# solenoidDriver.net
KiCad netlist of a schematic drawn in EAGLE
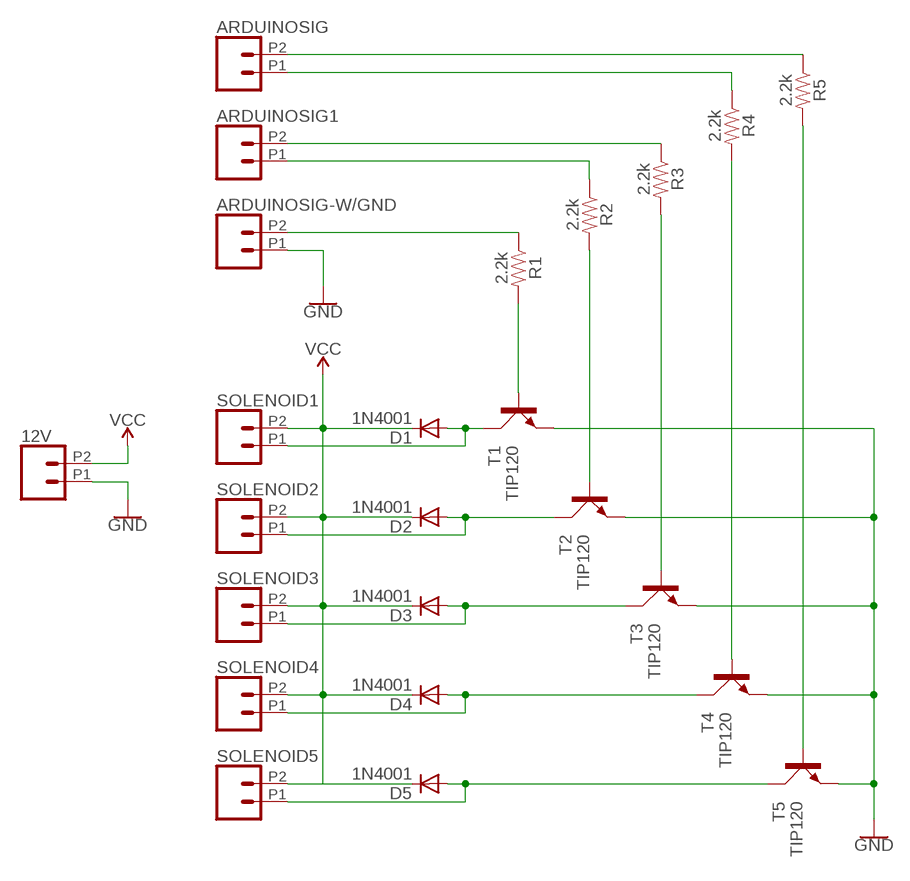
[diagram p0: schematic, sheet 1]

(export (version "E")
  (design (tool "Eeschema 10.0.6"))
  (components
    (comp (ref "12V")
      (value "CONN_022.54MM_SCREWTERM")
      (footprint "eagle-import:1X02_2.54_SCREWTERM")
      (libsource (lib "eagle-import") (part "CONN_022.54MM_SCREWTERM"))
    )
    (comp (ref "ARDUINOSIG")
      (value "CONN_022.54MM_SCREWTERM")
      (footprint "eagle-import:1X02_2.54_SCREWTERM")
      (libsource (lib "eagle-import") (part "CONN_022.54MM_SCREWTERM"))
    )
    (comp (ref "ARDUINOSIG-W/GND")
      (value "CONN_022.54MM_SCREWTERM")
      (footprint "eagle-import:1X02_2.54_SCREWTERM")
      (libsource (lib "eagle-import") (part "CONN_022.54MM_SCREWTERM"))
    )
    (comp (ref "ARDUINOSIG1")
      (value "CONN_022.54MM_SCREWTERM")
      (footprint "eagle-import:1X02_2.54_SCREWTERM")
      (libsource (lib "eagle-import") (part "CONN_022.54MM_SCREWTERM"))
    )
    (comp (ref "D1")
      (value "1N4001")
      (footprint "eagle-import:DO41-10")
      (libsource (lib "eagle-import") (part "1N4004"))
    )
    (comp (ref "D2")
      (value "1N4001")
      (footprint "eagle-import:DO41-10")
      (libsource (lib "eagle-import") (part "1N4004"))
    )
    (comp (ref "D3")
      (value "1N4001")
      (footprint "eagle-import:DO41-10")
      (libsource (lib "eagle-import") (part "1N4004"))
    )
    (comp (ref "D4")
      (value "1N4001")
      (footprint "eagle-import:DO41-10")
      (libsource (lib "eagle-import") (part "1N4004"))
    )
    (comp (ref "D5")
      (value "1N4001")
      (footprint "eagle-import:DO41-10")
      (libsource (lib "eagle-import") (part "1N4004"))
    )
    (comp (ref "R1")
      (value "2.2k")
      (footprint "eagle-import:AXIAL-0.3-KIT")
      (libsource (lib "eagle-import") (part "10KOHM-HORIZ_KIT-1/4W-1%"))
    )
    (comp (ref "R2")
      (value "2.2k")
      (footprint "eagle-import:AXIAL-0.3-KIT")
      (libsource (lib "eagle-import") (part "10KOHM-HORIZ_KIT-1/4W-1%"))
    )
    (comp (ref "R3")
      (value "2.2k")
      (footprint "eagle-import:AXIAL-0.3-KIT")
      (libsource (lib "eagle-import") (part "10KOHM-HORIZ_KIT-1/4W-1%"))
    )
    (comp (ref "R4")
      (value "2.2k")
      (footprint "eagle-import:AXIAL-0.3-KIT")
      (libsource (lib "eagle-import") (part "10KOHM-HORIZ_KIT-1/4W-1%"))
    )
    (comp (ref "R5")
      (value "2.2k")
      (footprint "eagle-import:AXIAL-0.3-KIT")
      (libsource (lib "eagle-import") (part "10KOHM-HORIZ_KIT-1/4W-1%"))
    )
    (comp (ref "SOLENOID1")
      (value "CONN_022.54MM_SCREWTERM")
      (footprint "eagle-import:1X02_2.54_SCREWTERM")
      (libsource (lib "eagle-import") (part "CONN_022.54MM_SCREWTERM"))
    )
    (comp (ref "SOLENOID2")
      (value "CONN_022.54MM_SCREWTERM")
      (footprint "eagle-import:1X02_2.54_SCREWTERM")
      (libsource (lib "eagle-import") (part "CONN_022.54MM_SCREWTERM"))
    )
    (comp (ref "SOLENOID3")
      (value "CONN_022.54MM_SCREWTERM")
      (footprint "eagle-import:1X02_2.54_SCREWTERM")
      (libsource (lib "eagle-import") (part "CONN_022.54MM_SCREWTERM"))
    )
    (comp (ref "SOLENOID4")
      (value "CONN_022.54MM_SCREWTERM")
      (footprint "eagle-import:1X02_2.54_SCREWTERM")
      (libsource (lib "eagle-import") (part "CONN_022.54MM_SCREWTERM"))
    )
    (comp (ref "SOLENOID5")
      (value "CONN_022.54MM_SCREWTERM")
      (footprint "eagle-import:1X02_2.54_SCREWTERM")
      (libsource (lib "eagle-import") (part "CONN_022.54MM_SCREWTERM"))
    )
    (comp (ref "T1")
      (value "TIP120")
      (footprint "eagle-import:TO220AH-NOHOLE")
      (libsource (lib "eagle-import") (part "TIP120-NOHOLE"))
    )
    (comp (ref "T2")
      (value "TIP120")
      (footprint "eagle-import:TO220AH-NOHOLE")
      (libsource (lib "eagle-import") (part "TIP120-NOHOLE"))
    )
    (comp (ref "T3")
      (value "TIP120")
      (footprint "eagle-import:TO220AH-NOHOLE")
      (libsource (lib "eagle-import") (part "TIP120-NOHOLE"))
    )
    (comp (ref "T4")
      (value "TIP120")
      (footprint "eagle-import:TO220AH-NOHOLE")
      (libsource (lib "eagle-import") (part "TIP120-NOHOLE"))
    )
    (comp (ref "T5")
      (value "TIP120")
      (footprint "eagle-import:TO220AH-NOHOLE")
      (libsource (lib "eagle-import") (part "TIP120-NOHOLE"))
    )
  )
  (nets
    (net (code "1") (name "GND") (class "Default")
      (node (ref "12V") (pin "P1") (pinfunction "1_P1") (pintype "passive"))
      (node (ref "ARDUINOSIG-W/GND") (pin "P1") (pinfunction "1_P1") (pintype "passive"))
      (node (ref "T1") (pin "E") (pinfunction "E_E") (pintype "passive"))
      (node (ref "T2") (pin "E") (pinfunction "E_E") (pintype "passive"))
      (node (ref "T3") (pin "E") (pinfunction "E_E") (pintype "passive"))
      (node (ref "T4") (pin "E") (pinfunction "E_E") (pintype "passive"))
      (node (ref "T5") (pin "E") (pinfunction "E_E") (pintype "passive"))
    )
    (net (code "2") (name "Net-(ARDUINOSIG-1)") (class "Default")
      (node (ref "ARDUINOSIG") (pin "P1") (pinfunction "1_P1") (pintype "passive"))
      (node (ref "R4") (pin "P$1") (pinfunction "1_P$1") (pintype "passive"))
    )
    (net (code "3") (name "Net-(ARDUINOSIG-2)") (class "Default")
      (node (ref "ARDUINOSIG") (pin "P2") (pinfunction "2_P2") (pintype "passive"))
      (node (ref "R5") (pin "P$1") (pinfunction "1_P$1") (pintype "passive"))
    )
    (net (code "4") (name "Net-(ARDUINOSIG-W/GND-2)") (class "Default")
      (node (ref "ARDUINOSIG-W/GND") (pin "P2") (pinfunction "2_P2") (pintype "passive"))
      (node (ref "R1") (pin "P$1") (pinfunction "1_P$1") (pintype "passive"))
    )
    (net (code "5") (name "Net-(ARDUINOSIG1-1)") (class "Default")
      (node (ref "ARDUINOSIG1") (pin "P1") (pinfunction "1_P1") (pintype "passive"))
      (node (ref "R2") (pin "P$1") (pinfunction "1_P$1") (pintype "passive"))
    )
    (net (code "6") (name "Net-(ARDUINOSIG1-2)") (class "Default")
      (node (ref "ARDUINOSIG1") (pin "P2") (pinfunction "2_P2") (pintype "passive"))
      (node (ref "R3") (pin "P$1") (pinfunction "1_P$1") (pintype "passive"))
    )
    (net (code "7") (name "Net-(R1-2)") (class "Default")
      (node (ref "R1") (pin "P$2") (pinfunction "2_P$2") (pintype "passive"))
      (node (ref "T1") (pin "B") (pinfunction "B_B") (pintype "passive"))
    )
    (net (code "8") (name "Net-(R2-2)") (class "Default")
      (node (ref "R2") (pin "P$2") (pinfunction "2_P$2") (pintype "passive"))
      (node (ref "T2") (pin "B") (pinfunction "B_B") (pintype "passive"))
    )
    (net (code "9") (name "Net-(R3-2)") (class "Default")
      (node (ref "R3") (pin "P$2") (pinfunction "2_P$2") (pintype "passive"))
      (node (ref "T3") (pin "B") (pinfunction "B_B") (pintype "passive"))
    )
    (net (code "10") (name "Net-(R4-2)") (class "Default")
      (node (ref "R4") (pin "P$2") (pinfunction "2_P$2") (pintype "passive"))
      (node (ref "T4") (pin "B") (pinfunction "B_B") (pintype "passive"))
    )
    (net (code "11") (name "Net-(R5-2)") (class "Default")
      (node (ref "R5") (pin "P$2") (pinfunction "2_P$2") (pintype "passive"))
      (node (ref "T5") (pin "B") (pinfunction "B_B") (pintype "passive"))
    )
    (net (code "12") (name "Net-(SOLENOID1-1)") (class "Default")
      (node (ref "D1") (pin "A") (pinfunction "A_A") (pintype "passive"))
      (node (ref "SOLENOID1") (pin "P1") (pinfunction "1_P1") (pintype "passive"))
      (node (ref "T1") (pin "C") (pinfunction "C_C") (pintype "passive"))
    )
    (net (code "13") (name "Net-(SOLENOID2-1)") (class "Default")
      (node (ref "D2") (pin "A") (pinfunction "A_A") (pintype "passive"))
      (node (ref "SOLENOID2") (pin "P1") (pinfunction "1_P1") (pintype "passive"))
      (node (ref "T2") (pin "C") (pinfunction "C_C") (pintype "passive"))
    )
    (net (code "14") (name "Net-(SOLENOID3-1)") (class "Default")
      (node (ref "D3") (pin "A") (pinfunction "A_A") (pintype "passive"))
      (node (ref "SOLENOID3") (pin "P1") (pinfunction "1_P1") (pintype "passive"))
      (node (ref "T3") (pin "C") (pinfunction "C_C") (pintype "passive"))
    )
    (net (code "15") (name "Net-(SOLENOID4-1)") (class "Default")
      (node (ref "D4") (pin "A") (pinfunction "A_A") (pintype "passive"))
      (node (ref "SOLENOID4") (pin "P1") (pinfunction "1_P1") (pintype "passive"))
      (node (ref "T4") (pin "C") (pinfunction "C_C") (pintype "passive"))
    )
    (net (code "16") (name "Net-(SOLENOID5-1)") (class "Default")
      (node (ref "D5") (pin "A") (pinfunction "A_A") (pintype "passive"))
      (node (ref "SOLENOID5") (pin "P1") (pinfunction "1_P1") (pintype "passive"))
      (node (ref "T5") (pin "C") (pinfunction "C_C") (pintype "passive"))
    )
    (net (code "17") (name "VCC") (class "Default")
      (node (ref "12V") (pin "P2") (pinfunction "2_P2") (pintype "passive"))
      (node (ref "D1") (pin "C") (pinfunction "C_C") (pintype "passive"))
      (node (ref "D2") (pin "C") (pinfunction "C_C") (pintype "passive"))
      (node (ref "D3") (pin "C") (pinfunction "C_C") (pintype "passive"))
      (node (ref "D4") (pin "C") (pinfunction "C_C") (pintype "passive"))
      (node (ref "D5") (pin "C") (pinfunction "C_C") (pintype "passive"))
      (node (ref "SOLENOID1") (pin "P2") (pinfunction "2_P2") (pintype "passive"))
      (node (ref "SOLENOID2") (pin "P2") (pinfunction "2_P2") (pintype "passive"))
      (node (ref "SOLENOID3") (pin "P2") (pinfunction "2_P2") (pintype "passive"))
      (node (ref "SOLENOID4") (pin "P2") (pinfunction "2_P2") (pintype "passive"))
      (node (ref "SOLENOID5") (pin "P2") (pinfunction "2_P2") (pintype "passive"))
    )
  )
)
